# Power_PMIC.net
KiCad netlist of a schematic drawn in Altium Designer
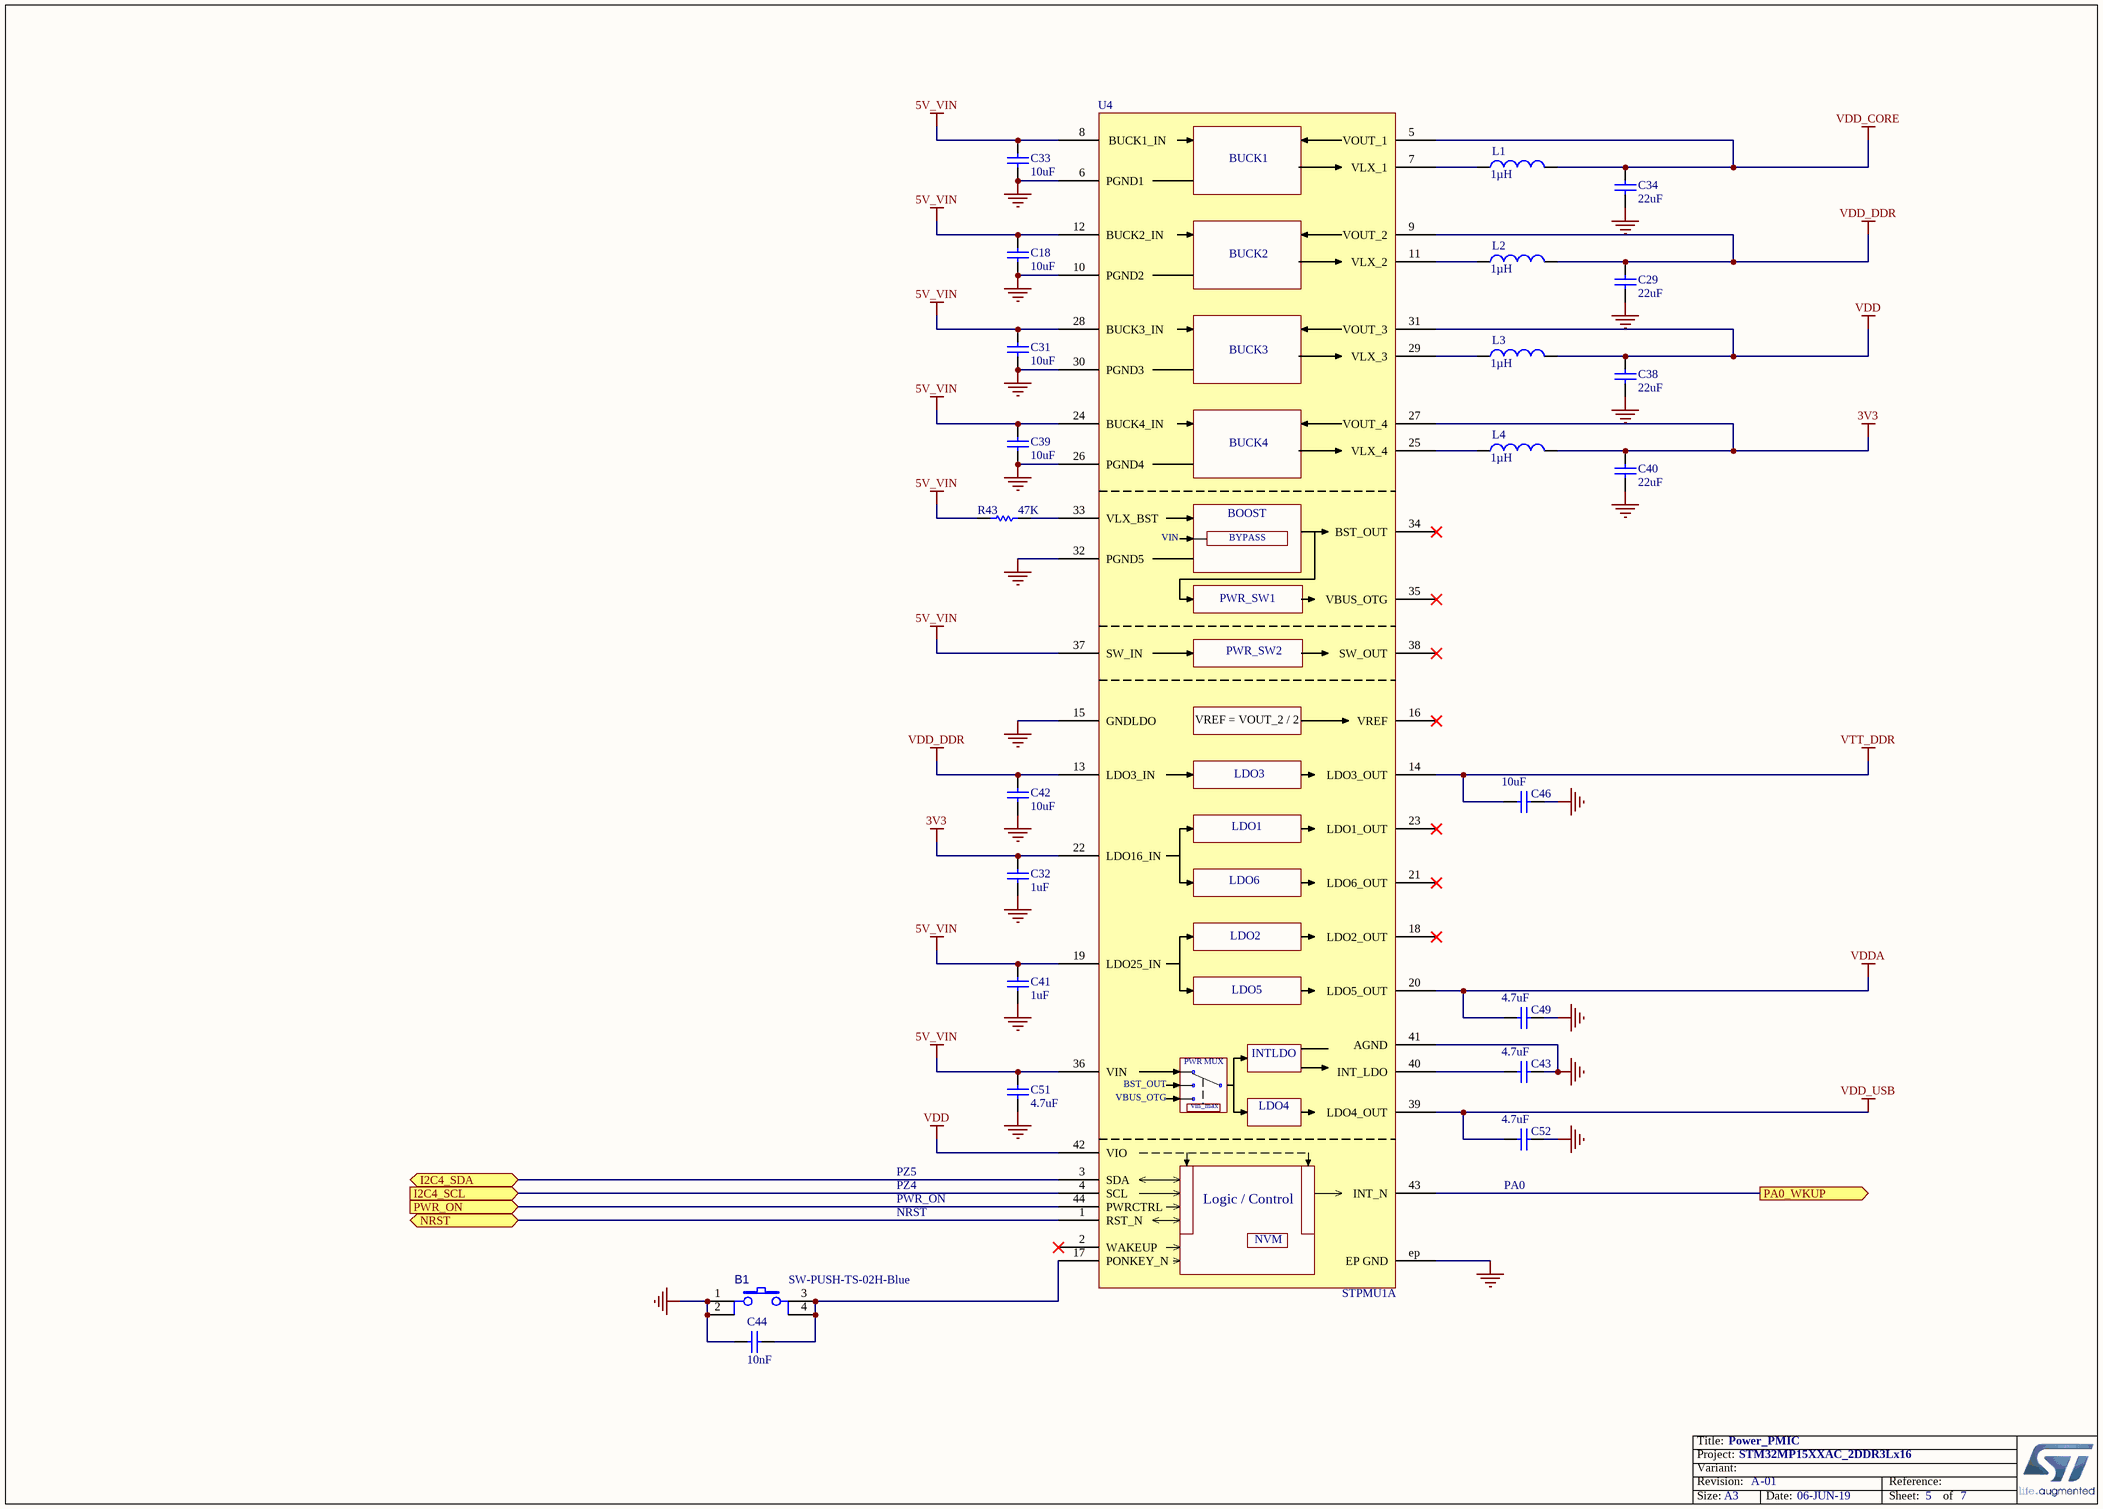
[diagram p0: Power_PMIC.SchDoc]

(export (version "E")
  (design (tool "Eeschema 10.0.6"))
  (components
    (comp (ref "B1")
      (value "SW-PUSH-TS-02H-Blue")
      (footprint "SWI_JIUBABA_C-TS-02H-2-5-B-V-T_R_BLUE")
      (description "Switch HW SMD blue")
      (fields
        (field (name "INTERNAL_PART_NUMBER") "MCD-00172")
        (field (name "MANUFACTURER_PART_NUMBER") "C-TS-02H-2.5-B-V-T/R BLUE")
        (field (name "PROVIDED_BY") "SUBCO")
      )
      (libsource (lib "MCD_PARTS_database") (part "SW-PUSH-TS-02H-Blue"))
    )
    (comp (ref "C18")
      (value "10uF")
      (footprint "C0603")
      (description "Capacitor, MLCC, 10uF, 10V, X5R, 10%, 0603, T=0,8mm")
      (fields
        (field (name "INTERNAL_PART_NUMBER") "MCD-00099")
        (field (name "MANUFACTURER_PART_NUMBER") "GRM188R61A106KE69D")
        (field (name "PROVIDED_BY") "SUBCO")
      )
      (libsource (lib "MCD_PARTS_database") (part "Capacitor"))
    )
    (comp (ref "C29")
      (value "22uF")
      (footprint "C0603")
      (description "Capacitor, MLCC, 22uF, 6V3, X5R, 20%, 0603, T=0,8mm")
      (fields
        (field (name "INTERNAL_PART_NUMBER") "MCD-00100")
        (field (name "MANUFACTURER_PART_NUMBER") "GRM188R60J226MEA0J")
        (field (name "PROVIDED_BY") "SUBCO")
      )
      (libsource (lib "MCD_PARTS_database") (part "Capacitor"))
    )
    (comp (ref "C31")
      (value "10uF")
      (footprint "C0603")
      (description "Capacitor, MLCC, 10uF, 10V, X5R, 10%, 0603, T=0,8mm")
      (fields
        (field (name "INTERNAL_PART_NUMBER") "MCD-00099")
        (field (name "MANUFACTURER_PART_NUMBER") "GRM188R61A106KE69D")
        (field (name "PROVIDED_BY") "SUBCO")
      )
      (libsource (lib "MCD_PARTS_database") (part "Capacitor"))
    )
    (comp (ref "C32")
      (value "1uF")
      (footprint "C0402")
      (description "Capacitor, MLCC, 1uF, 6V3, X5R, 10%, 0402, T=0,5mm")
      (fields
        (field (name "INTERNAL_PART_NUMBER") "MCD-00095")
        (field (name "MANUFACTURER_PART_NUMBER") "GRM155R60J105KE19")
        (field (name "PROVIDED_BY") "SUBCO")
      )
      (libsource (lib "MCD_PARTS_database") (part "Capacitor"))
    )
    (comp (ref "C33")
      (value "10uF")
      (footprint "C0603")
      (description "Capacitor, MLCC, 10uF, 10V, X5R, 10%, 0603, T=0,8mm")
      (fields
        (field (name "INTERNAL_PART_NUMBER") "MCD-00099")
        (field (name "MANUFACTURER_PART_NUMBER") "GRM188R61A106KE69D")
        (field (name "PROVIDED_BY") "SUBCO")
      )
      (libsource (lib "MCD_PARTS_database") (part "Capacitor"))
    )
    (comp (ref "C34")
      (value "22uF")
      (footprint "C0603")
      (description "Capacitor, MLCC, 22uF, 6V3, X5R, 20%, 0603, T=0,8mm")
      (fields
        (field (name "INTERNAL_PART_NUMBER") "MCD-00100")
        (field (name "MANUFACTURER_PART_NUMBER") "GRM188R60J226MEA0J")
        (field (name "PROVIDED_BY") "SUBCO")
      )
      (libsource (lib "MCD_PARTS_database") (part "Capacitor"))
    )
    (comp (ref "C38")
      (value "22uF")
      (footprint "C0603")
      (description "Capacitor, MLCC, 22uF, 6V3, X5R, 20%, 0603, T=0,8mm")
      (fields
        (field (name "INTERNAL_PART_NUMBER") "MCD-00100")
        (field (name "MANUFACTURER_PART_NUMBER") "GRM188R60J226MEA0J")
        (field (name "PROVIDED_BY") "SUBCO")
      )
      (libsource (lib "MCD_PARTS_database") (part "Capacitor"))
    )
    (comp (ref "C39")
      (value "10uF")
      (footprint "C0603")
      (description "Capacitor, MLCC, 10uF, 10V, X5R, 10%, 0603, T=0,8mm")
      (fields
        (field (name "INTERNAL_PART_NUMBER") "MCD-00099")
        (field (name "MANUFACTURER_PART_NUMBER") "GRM188R61A106KE69D")
        (field (name "PROVIDED_BY") "SUBCO")
      )
      (libsource (lib "MCD_PARTS_database") (part "Capacitor"))
    )
    (comp (ref "C40")
      (value "22uF")
      (footprint "C0603")
      (description "Capacitor, MLCC, 22uF, 6V3, X5R, 20%, 0603, T=0,8mm")
      (fields
        (field (name "INTERNAL_PART_NUMBER") "MCD-00100")
        (field (name "MANUFACTURER_PART_NUMBER") "GRM188R60J226MEA0J")
        (field (name "PROVIDED_BY") "SUBCO")
      )
      (libsource (lib "MCD_PARTS_database") (part "Capacitor"))
    )
    (comp (ref "C41")
      (value "1uF")
      (footprint "C0402")
      (description "Capacitor, MLCC, 1uF, 6V3, X5R, 10%, 0402, T=0,5mm")
      (fields
        (field (name "INTERNAL_PART_NUMBER") "MCD-00095")
        (field (name "MANUFACTURER_PART_NUMBER") "GRM155R60J105KE19")
        (field (name "PROVIDED_BY") "SUBCO")
      )
      (libsource (lib "MCD_PARTS_database") (part "Capacitor"))
    )
    (comp (ref "C42")
      (value "10uF")
      (footprint "C0603")
      (description "Capacitor, MLCC, 10uF, 10V, X5R, 10%, 0603, T=0,8mm")
      (fields
        (field (name "INTERNAL_PART_NUMBER") "MCD-00099")
        (field (name "MANUFACTURER_PART_NUMBER") "GRM188R61A106KE69D")
        (field (name "PROVIDED_BY") "SUBCO")
      )
      (libsource (lib "MCD_PARTS_database") (part "Capacitor"))
    )
    (comp (ref "C43")
      (value "4.7uF")
      (footprint "C0402")
      (description "Capacitor, MLCC, 4.7uF, 6V3, X5R, 20%, 0402, T=0,5mm")
      (fields
        (field (name "INTERNAL_PART_NUMBER") "MCD-00096")
        (field (name "MANUFACTURER_PART_NUMBER") "GRM155R60J475ME87")
        (field (name "PROVIDED_BY") "SUBCO")
      )
      (libsource (lib "MCD_PARTS_database") (part "Capacitor"))
    )
    (comp (ref "C44")
      (value "10nF")
      (footprint "C0402")
      (description "Capacitor, MLCC, 10nF, 16V, X7R, 10%, 0402, T=0.5mm")
      (fields
        (field (name "INTERNAL_PART_NUMBER") "MCD-00011")
        (field (name "MANUFACTURER_PART_NUMBER") "CC0402KRX7R7BB103")
        (field (name "PROVIDED_BY") "SUBCO")
      )
      (libsource (lib "MCD_PARTS_database") (part "Capacitor"))
    )
    (comp (ref "C46")
      (value "10uF")
      (footprint "C0603")
      (description "Capacitor, MLCC, 10uF, 10V, X5R, 10%, 0603, T=0,8mm")
      (fields
        (field (name "INTERNAL_PART_NUMBER") "MCD-00099")
        (field (name "MANUFACTURER_PART_NUMBER") "GRM188R61A106KE69D")
        (field (name "PROVIDED_BY") "Subcon")
      )
      (libsource (lib "MCD_PARTS_database") (part "Capacitor"))
    )
    (comp (ref "C49")
      (value "4.7uF")
      (footprint "C0402")
      (description "Capacitor, MLCC, 4.7uF, 6V3, X5R, 20%, 0402, T=0,5mm")
      (fields
        (field (name "INTERNAL_PART_NUMBER") "MCD-00096")
        (field (name "MANUFACTURER_PART_NUMBER") "GRM155R60J475ME87")
        (field (name "PROVIDED_BY") "SUBCO")
      )
      (libsource (lib "MCD_PARTS_database") (part "Capacitor"))
    )
    (comp (ref "C51")
      (value "4.7uF")
      (footprint "C0402")
      (description "Capacitor, MLCC, 4.7uF, 6V3, X5R, 20%, 0402, T=0,5mm")
      (fields
        (field (name "INTERNAL_PART_NUMBER") "MCD-00096")
        (field (name "MANUFACTURER_PART_NUMBER") "GRM155R60J475ME87")
        (field (name "PROVIDED_BY") "SUBCO")
      )
      (libsource (lib "MCD_PARTS_database") (part "Capacitor"))
    )
    (comp (ref "C52")
      (value "4.7uF")
      (footprint "C0402")
      (description "Capacitor, MLCC, 4.7uF, 6V3, X5R, 20%, 0402, T=0,5mm")
      (fields
        (field (name "INTERNAL_PART_NUMBER") "MCD-00096")
        (field (name "MANUFACTURER_PART_NUMBER") "GRM155R60J475ME87")
        (field (name "PROVIDED_BY") "SUBCO")
      )
      (libsource (lib "MCD_PARTS_database") (part "Capacitor"))
    )
    (comp (ref "L1")
      (value "1µH")
      (footprint "IND_2520_TOKO_DFE252012P")
      (description "Power Inductor ,1µH,4.3A max,+-20%,0.042ohm,2520")
      (fields
        (field (name "INTERNAL_PART_NUMBER") "MCD-01122")
        (field (name "MANUFACTURER_PART_NUMBER") "DFE252012P-1ROM=P2")
        (field (name "PROVIDED_BY") "SUBCO")
      )
      (libsource (lib "MCD_PARTS_database") (part "IND_1uH_42mohm_3.2A"))
    )
    (comp (ref "L2")
      (value "1µH")
      (footprint "IND_2520_TOKO_DFE252012P")
      (description "Power Inductor ,1µH,4.3A max,+-20%,0.042ohm,2520")
      (fields
        (field (name "INTERNAL_PART_NUMBER") "MCD-01122")
        (field (name "MANUFACTURER_PART_NUMBER") "DFE252012P-1ROM=P2")
        (field (name "PROVIDED_BY") "SUBCO")
      )
      (libsource (lib "MCD_PARTS_database") (part "IND_1uH_42mohm_3.2A"))
    )
    (comp (ref "L3")
      (value "1µH")
      (footprint "IND_2520_TOKO_DFE252012P")
      (description "Power Inductor ,1µH,4.3A max,+-20%,0.042ohm,2520")
      (fields
        (field (name "INTERNAL_PART_NUMBER") "MCD-01122")
        (field (name "MANUFACTURER_PART_NUMBER") "DFE252012P-1ROM=P2")
        (field (name "PROVIDED_BY") "SUBCO")
      )
      (libsource (lib "MCD_PARTS_database") (part "IND_1uH_42mohm_3.2A"))
    )
    (comp (ref "L4")
      (value "1µH")
      (footprint "IND_2520_TOKO_DFE252012P")
      (description "Power Inductor ,1µH,4.3A max,+-20%,0.042ohm,2520")
      (fields
        (field (name "INTERNAL_PART_NUMBER") "MCD-01122")
        (field (name "MANUFACTURER_PART_NUMBER") "DFE252012P-1ROM=P2")
        (field (name "PROVIDED_BY") "SUBCO")
      )
      (libsource (lib "MCD_PARTS_database") (part "IND_1uH_42mohm_3.2A"))
    )
    (comp (ref "R43")
      (value "47K")
      (footprint "R0402")
      (description "Resistor,47K,0402,1%,1/16W")
      (fields
        (field (name "INTERNAL_PART_NUMBER") "MCD-00063")
        (field (name "MANUFACTURER_PART_NUMBER") "RC0402FR-0747KL")
        (field (name "PROVIDED_BY") "SUBCO")
      )
      (libsource (lib "MCD_PARTS_database") (part "Resistor"))
    )
    (comp (ref "U4")
      (value "STPMU1A")
      (footprint "ICC_WFQFN44-EPAD_5X6_P040")
      (description "STM PMIC WFQFN 5.0x6.0x0.80 44L 0.4 pitch")
      (fields
        (field (name "INTERNAL_PART_NUMBER") "MCD-00303")
        (field (name "MANUFACTURER") "STMICROELECTRONICS")
        (field (name "PROVIDED_BY") "SUBCO with ST control")
      )
      (libsource (lib "MCD_PARTS_database") (part "STPMU1A"))
    )
  )
  (nets
    (net (code "1") (name "/I2C4_SCL") (class "Default")
      (node (ref "U4") (pin "4") (pinfunction "SCL_4") (pintype "passive"))
    )
    (net (code "2") (name "/I2C4_SDA") (class "Default")
      (node (ref "U4") (pin "3") (pinfunction "SDA_3") (pintype "passive"))
    )
    (net (code "3") (name "/NRST") (class "Default")
      (node (ref "U4") (pin "1") (pinfunction "RST_N_1") (pintype "passive"))
    )
    (net (code "4") (name "/PA0_WKUP") (class "Default")
      (node (ref "U4") (pin "43") (pinfunction "INT_N_43") (pintype "passive"))
    )
    (net (code "5") (name "/PWR_ON") (class "Default")
      (node (ref "U4") (pin "44") (pinfunction "PWRCTRL_44") (pintype "passive"))
    )
    (net (code "6") (name "3V3") (class "Default")
      (node (ref "C32") (pin "2") (pinfunction "2_2") (pintype "passive"))
      (node (ref "C40") (pin "2") (pinfunction "2_2") (pintype "passive"))
      (node (ref "L4") (pin "2") (pinfunction "2_2") (pintype "passive"))
      (node (ref "U4") (pin "22") (pinfunction "LDO16_IN_22") (pintype "passive"))
      (node (ref "U4") (pin "27") (pinfunction "VOUT_4_27") (pintype "passive"))
    )
    (net (code "7") (name "5V_VIN") (class "Default")
      (node (ref "C18") (pin "2") (pinfunction "2_2") (pintype "passive"))
      (node (ref "C31") (pin "2") (pinfunction "2_2") (pintype "passive"))
      (node (ref "C33") (pin "2") (pinfunction "2_2") (pintype "passive"))
      (node (ref "C39") (pin "2") (pinfunction "2_2") (pintype "passive"))
      (node (ref "C41") (pin "2") (pinfunction "2_2") (pintype "passive"))
      (node (ref "C51") (pin "2") (pinfunction "2_2") (pintype "passive"))
      (node (ref "R43") (pin "2") (pinfunction "2_2") (pintype "passive"))
      (node (ref "U4") (pin "12") (pinfunction "BUCK2_IN_12") (pintype "passive"))
      (node (ref "U4") (pin "19") (pinfunction "LDO25_IN_19") (pintype "passive"))
      (node (ref "U4") (pin "24") (pinfunction "BUCK4_IN_24") (pintype "passive"))
      (node (ref "U4") (pin "28") (pinfunction "BUCK3_IN_28") (pintype "passive"))
      (node (ref "U4") (pin "36") (pinfunction "VIN_36") (pintype "passive"))
      (node (ref "U4") (pin "37") (pinfunction "SW_IN_37") (pintype "passive"))
      (node (ref "U4") (pin "8") (pinfunction "BUCK1_IN_8") (pintype "passive"))
    )
    (net (code "8") (name "GND") (class "Default")
      (node (ref "B1") (pin "1") (pinfunction "1_1") (pintype "passive"))
      (node (ref "B1") (pin "2") (pinfunction "2_2") (pintype "passive"))
      (node (ref "C18") (pin "1") (pinfunction "1_1") (pintype "passive"))
      (node (ref "C29") (pin "1") (pinfunction "1_1") (pintype "passive"))
      (node (ref "C31") (pin "1") (pinfunction "1_1") (pintype "passive"))
      (node (ref "C32") (pin "1") (pinfunction "1_1") (pintype "passive"))
      (node (ref "C33") (pin "1") (pinfunction "1_1") (pintype "passive"))
      (node (ref "C34") (pin "1") (pinfunction "1_1") (pintype "passive"))
      (node (ref "C38") (pin "1") (pinfunction "1_1") (pintype "passive"))
      (node (ref "C39") (pin "1") (pinfunction "1_1") (pintype "passive"))
      (node (ref "C40") (pin "1") (pinfunction "1_1") (pintype "passive"))
      (node (ref "C41") (pin "1") (pinfunction "1_1") (pintype "passive"))
      (node (ref "C42") (pin "1") (pinfunction "1_1") (pintype "passive"))
      (node (ref "C43") (pin "2") (pinfunction "2_2") (pintype "passive"))
      (node (ref "C44") (pin "1") (pinfunction "1_1") (pintype "passive"))
      (node (ref "C46") (pin "1") (pinfunction "1_1") (pintype "passive"))
      (node (ref "C49") (pin "1") (pinfunction "1_1") (pintype "passive"))
      (node (ref "C51") (pin "1") (pinfunction "1_1") (pintype "passive"))
      (node (ref "C52") (pin "1") (pinfunction "1_1") (pintype "passive"))
      (node (ref "U4") (pin "10") (pinfunction "PGND2_10") (pintype "passive"))
      (node (ref "U4") (pin "15") (pinfunction "GNDLDO_15") (pintype "passive"))
      (node (ref "U4") (pin "26") (pinfunction "PGND4_26") (pintype "passive"))
      (node (ref "U4") (pin "30") (pinfunction "PGND3_30") (pintype "passive"))
      (node (ref "U4") (pin "32") (pinfunction "PGND5_32") (pintype "passive"))
      (node (ref "U4") (pin "41") (pinfunction "AGND_41") (pintype "passive"))
      (node (ref "U4") (pin "6") (pinfunction "PGND1_6") (pintype "passive"))
      (node (ref "U4") (pin "ep") (pinfunction "EP_GND_ep") (pintype "passive"))
    )
    (net (code "9") (name "Net-(U4-INT_LDO)") (class "Default")
      (node (ref "C43") (pin "1") (pinfunction "1_1") (pintype "passive"))
      (node (ref "U4") (pin "40") (pinfunction "INT_LDO_40") (pintype "passive"))
    )
    (net (code "10") (name "Net-(U4-PONKEY_N)") (class "Default")
      (node (ref "B1") (pin "3") (pinfunction "3_3") (pintype "passive"))
      (node (ref "B1") (pin "4") (pinfunction "4_4") (pintype "passive"))
      (node (ref "C44") (pin "2") (pinfunction "2_2") (pintype "passive"))
      (node (ref "U4") (pin "17") (pinfunction "PONKEY_N_17") (pintype "passive"))
    )
    (net (code "11") (name "Net-(U4-VLX_1)") (class "Default")
      (node (ref "L1") (pin "1") (pinfunction "1_1") (pintype "passive"))
      (node (ref "U4") (pin "7") (pinfunction "VLX_1_7") (pintype "passive"))
    )
    (net (code "12") (name "Net-(U4-VLX_2)") (class "Default")
      (node (ref "L2") (pin "1") (pinfunction "1_1") (pintype "passive"))
      (node (ref "U4") (pin "11") (pinfunction "VLX_2_11") (pintype "passive"))
    )
    (net (code "13") (name "Net-(U4-VLX_3)") (class "Default")
      (node (ref "L3") (pin "1") (pinfunction "1_1") (pintype "passive"))
      (node (ref "U4") (pin "29") (pinfunction "VLX_3_29") (pintype "passive"))
    )
    (net (code "14") (name "Net-(U4-VLX_4)") (class "Default")
      (node (ref "L4") (pin "1") (pinfunction "1_1") (pintype "passive"))
      (node (ref "U4") (pin "25") (pinfunction "VLX_4_25") (pintype "passive"))
    )
    (net (code "15") (name "Net-(U4-VLX_BST)") (class "Default")
      (node (ref "R43") (pin "1") (pinfunction "1_1") (pintype "passive"))
      (node (ref "U4") (pin "33") (pinfunction "VLX_BST_33") (pintype "passive"))
    )
    (net (code "16") (name "VDD") (class "Default")
      (node (ref "C38") (pin "2") (pinfunction "2_2") (pintype "passive"))
      (node (ref "L3") (pin "2") (pinfunction "2_2") (pintype "passive"))
      (node (ref "U4") (pin "31") (pinfunction "VOUT_3_31") (pintype "passive"))
      (node (ref "U4") (pin "42") (pinfunction "VIO_42") (pintype "passive"))
    )
    (net (code "17") (name "VDDA") (class "Default")
      (node (ref "C49") (pin "2") (pinfunction "2_2") (pintype "passive"))
      (node (ref "U4") (pin "20") (pinfunction "LDO5_OUT_20") (pintype "passive"))
    )
    (net (code "18") (name "VDD_CORE") (class "Default")
      (node (ref "C34") (pin "2") (pinfunction "2_2") (pintype "passive"))
      (node (ref "L1") (pin "2") (pinfunction "2_2") (pintype "passive"))
      (node (ref "U4") (pin "5") (pinfunction "VOUT_1_5") (pintype "passive"))
    )
    (net (code "19") (name "VDD_DDR") (class "Default")
      (node (ref "C29") (pin "2") (pinfunction "2_2") (pintype "passive"))
      (node (ref "C42") (pin "2") (pinfunction "2_2") (pintype "passive"))
      (node (ref "L2") (pin "2") (pinfunction "2_2") (pintype "passive"))
      (node (ref "U4") (pin "13") (pinfunction "LDO3_IN_13") (pintype "passive"))
      (node (ref "U4") (pin "9") (pinfunction "VOUT_2_9") (pintype "passive"))
    )
    (net (code "20") (name "VDD_USB") (class "Default")
      (node (ref "C52") (pin "2") (pinfunction "2_2") (pintype "passive"))
      (node (ref "U4") (pin "39") (pinfunction "LDO4_OUT_39") (pintype "passive"))
    )
    (net (code "21") (name "VTT_DDR") (class "Default")
      (node (ref "C46") (pin "2") (pinfunction "2_2") (pintype "passive"))
      (node (ref "U4") (pin "14") (pinfunction "LDO3_OUT_14") (pintype "passive"))
    )
    (net (code "22") (name "unconnected-(U4-BST_OUT-Pad34)") (class "Default")
      (node (ref "U4") (pin "34") (pinfunction "BST_OUT_34") (pintype "passive+no_connect"))
    )
    (net (code "23") (name "unconnected-(U4-LDO1_OUT-Pad23)") (class "Default")
      (node (ref "U4") (pin "23") (pinfunction "LDO1_OUT_23") (pintype "passive+no_connect"))
    )
    (net (code "24") (name "unconnected-(U4-LDO2_OUT-Pad18)") (class "Default")
      (node (ref "U4") (pin "18") (pinfunction "LDO2_OUT_18") (pintype "passive+no_connect"))
    )
    (net (code "25") (name "unconnected-(U4-LDO6_OUT-Pad21)") (class "Default")
      (node (ref "U4") (pin "21") (pinfunction "LDO6_OUT_21") (pintype "passive+no_connect"))
    )
    (net (code "26") (name "unconnected-(U4-SW_OUT-Pad38)") (class "Default")
      (node (ref "U4") (pin "38") (pinfunction "SW_OUT_38") (pintype "passive+no_connect"))
    )
    (net (code "27") (name "unconnected-(U4-VBUS_OTG-Pad35)") (class "Default")
      (node (ref "U4") (pin "35") (pinfunction "VBUS_OTG_35") (pintype "passive+no_connect"))
    )
    (net (code "28") (name "unconnected-(U4-VREF-Pad16)") (class "Default")
      (node (ref "U4") (pin "16") (pinfunction "VREF_16") (pintype "passive+no_connect"))
    )
    (net (code "29") (name "unconnected-(U4-WAKEUP-Pad2)") (class "Default")
      (node (ref "U4") (pin "2") (pinfunction "WAKEUP_2") (pintype "passive+no_connect"))
    )
  )
)
